# PPG_sensor.net
KiCad netlist of a schematic drawn in Altium Designer
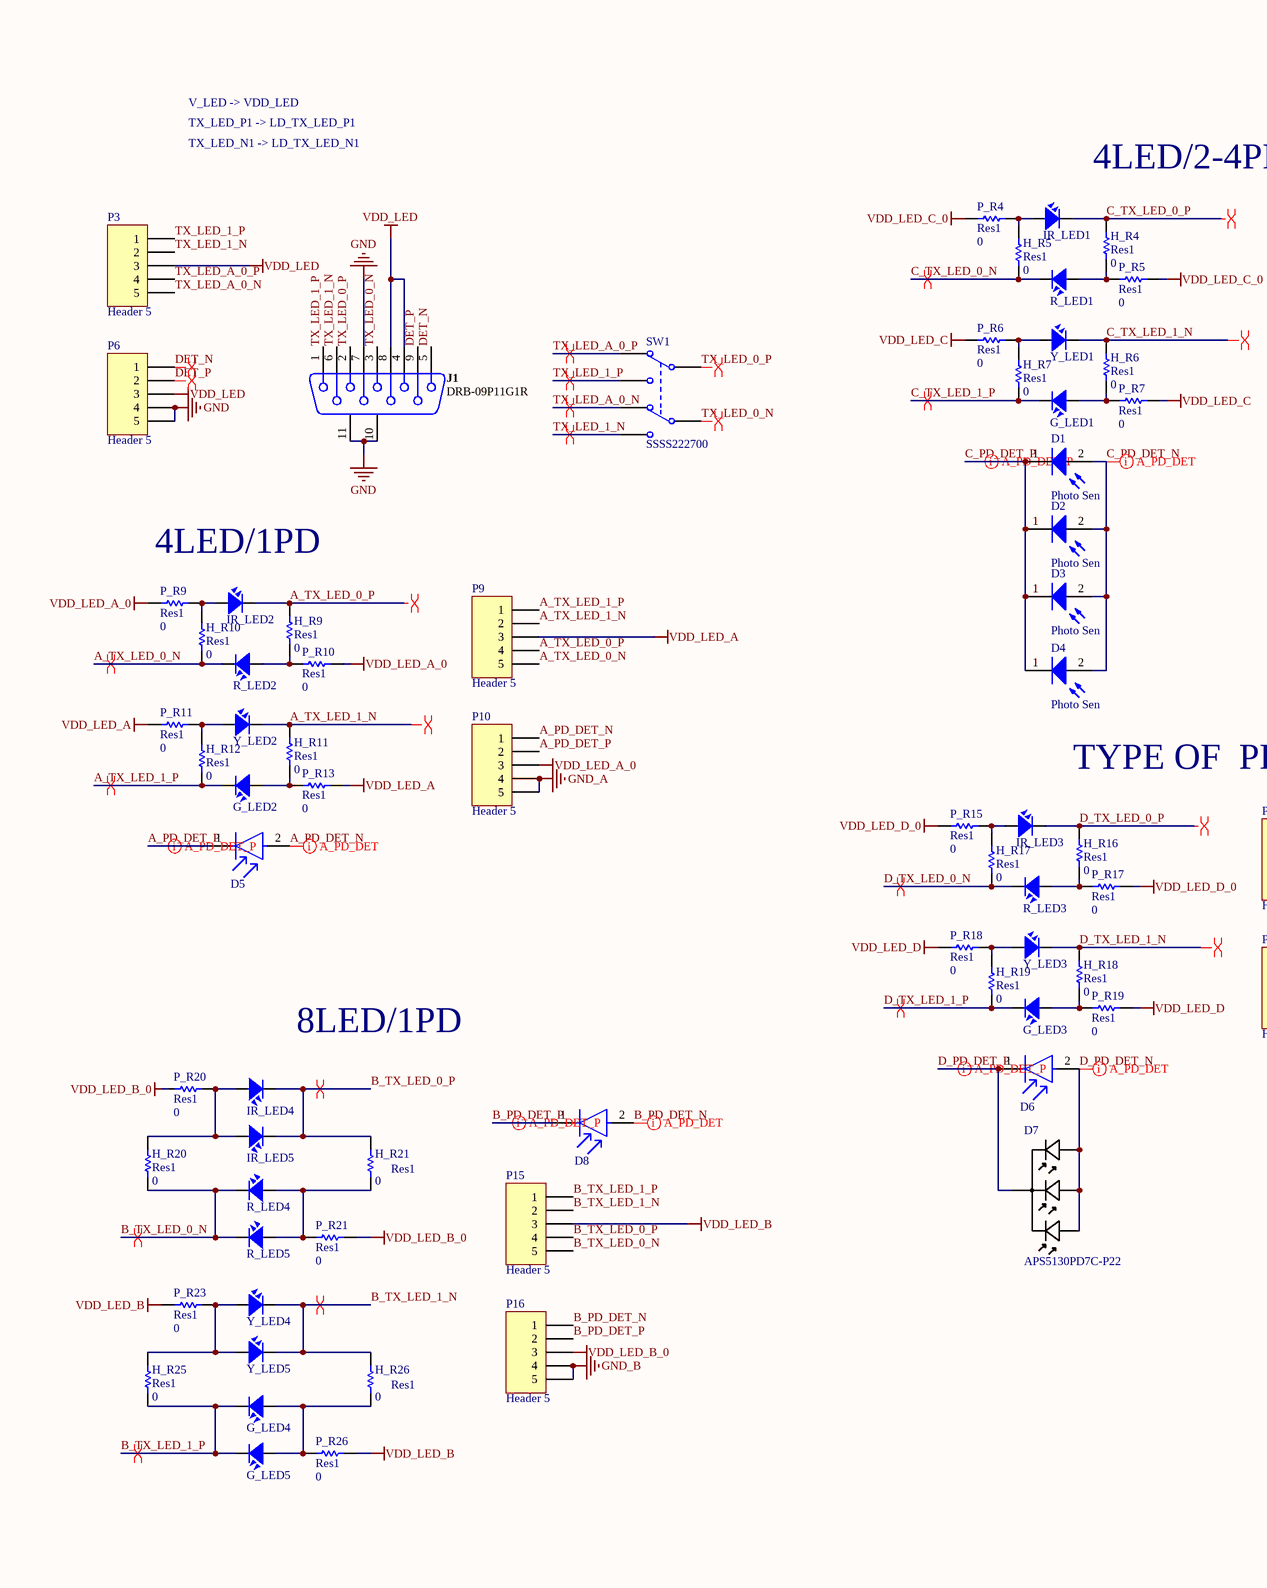
[diagram p0: PPG_sensor.SchDoc, left]
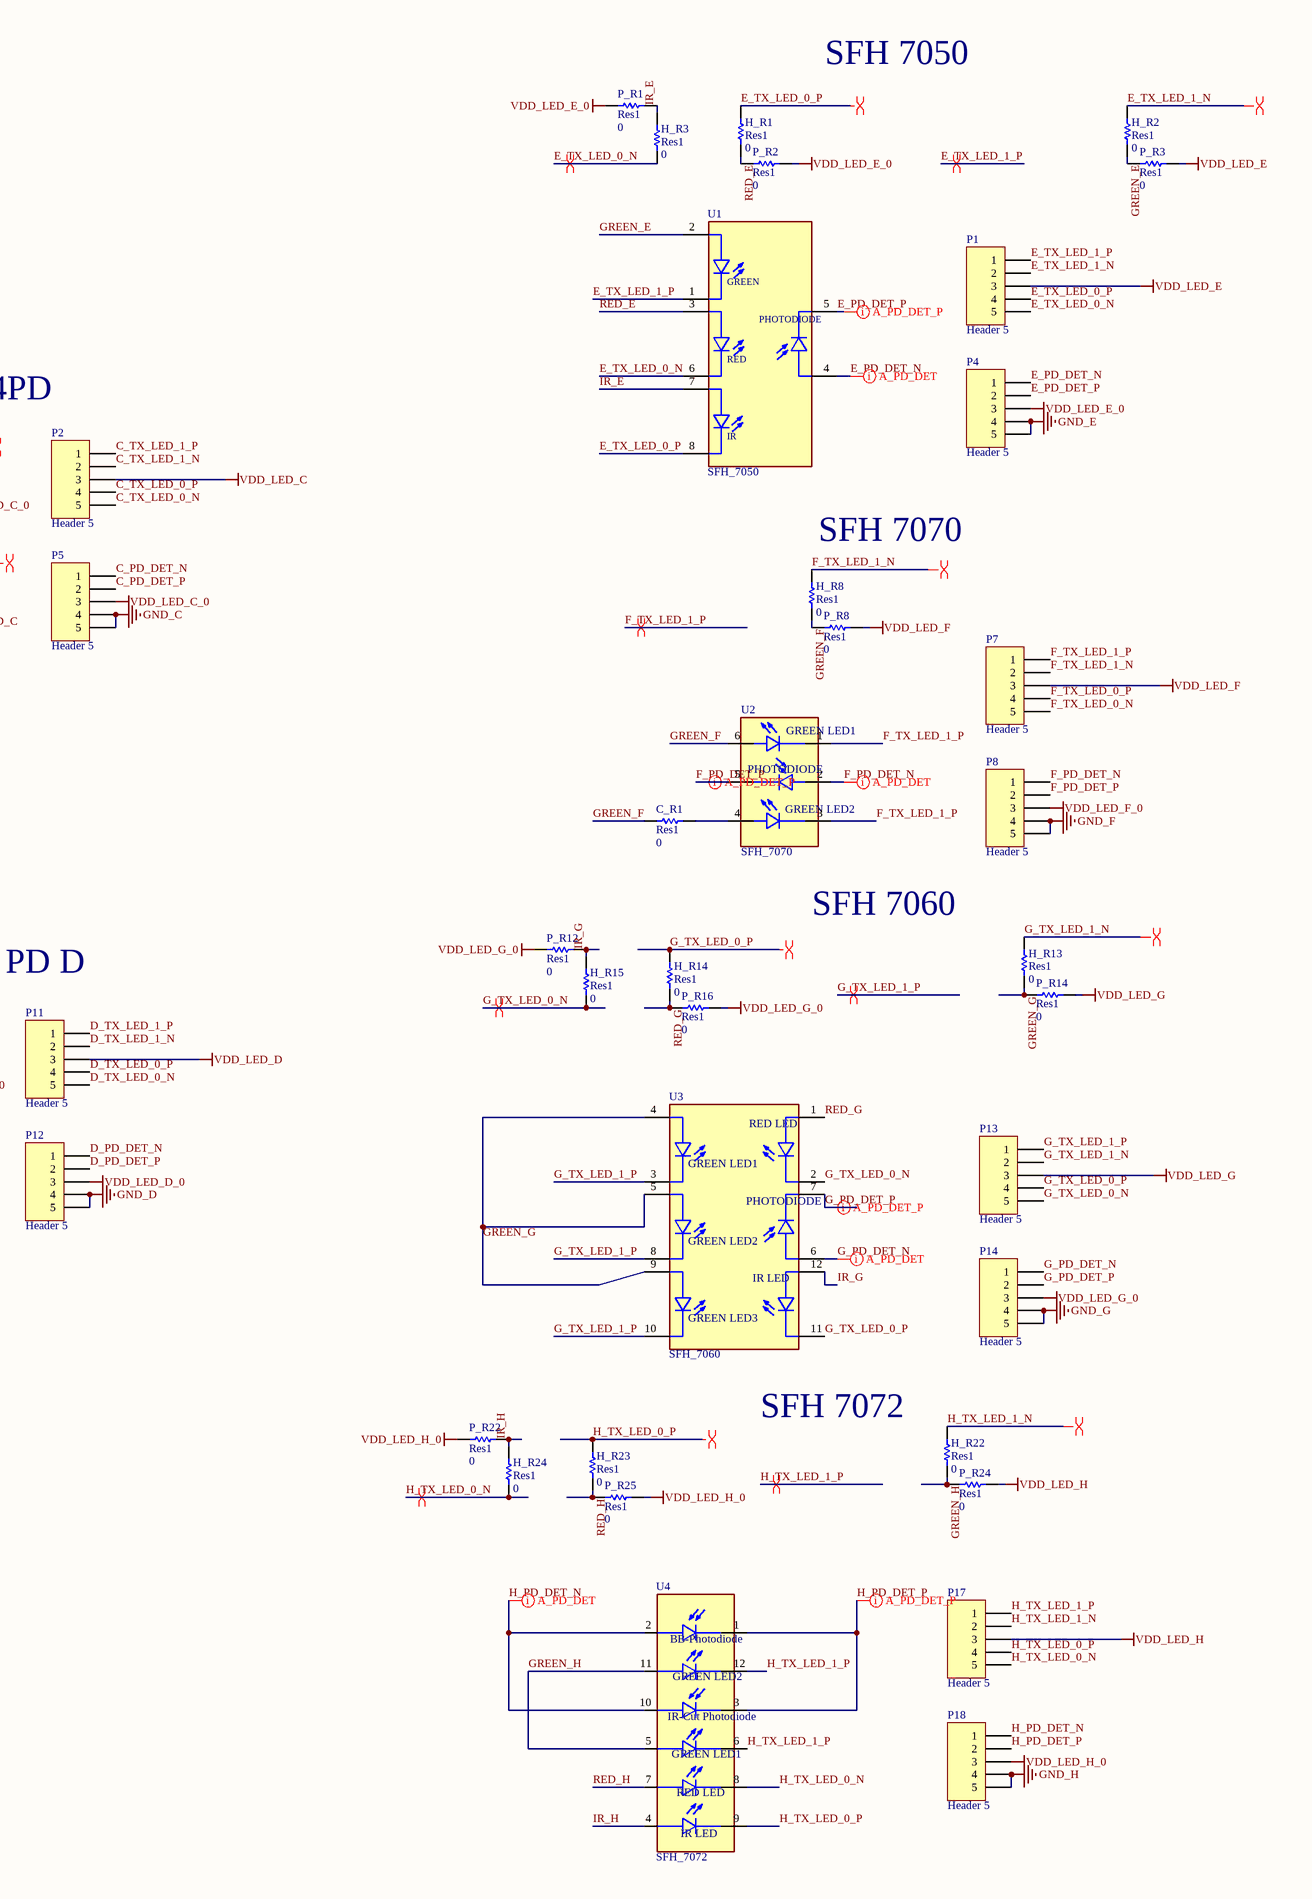
[diagram p1: PPG_sensor.SchDoc, right]

(export (version "E")
  (design (tool "Eeschema 10.0.6"))
  (components
    (comp (ref "C_R1")
      (value "Res1")
      (footprint "RES-SMD-0603")
      (description "Resistor")
      (fields (field (name "ALTIUM_VALUE") "0"))
      (libsource (lib "Miscellaneous Devices") (part "Res1"))
    )
    (comp (ref "D1")
      (value "Photo Sen")
      (footprint "PD_2704")
      (description "Photosensitive Diode")
      (libsource (lib "Miscellaneous Devices") (part "Photo Sen"))
    )
    (comp (ref "D2")
      (value "Photo Sen")
      (footprint "PD_2704")
      (description "Photosensitive Diode")
      (libsource (lib "Miscellaneous Devices") (part "Photo Sen"))
    )
    (comp (ref "D3")
      (value "Photo Sen")
      (footprint "PD_2704")
      (description "Photosensitive Diode")
      (libsource (lib "Miscellaneous Devices") (part "Photo Sen"))
    )
    (comp (ref "D4")
      (value "Photo Sen")
      (footprint "PD_2704")
      (description "Photosensitive Diode")
      (libsource (lib "Miscellaneous Devices") (part "Photo Sen"))
    )
    (comp (ref "D5")
      (value "SFH_2704")
      (footprint "OSRAM_Opto_Semiconductors_SFH_2704_MFG")
      (libsource (lib "Diode_OSRAM_Opto_Semiconductors_SFH_2704_eec") (part "SFH_2704"))
    )
    (comp (ref "D6")
      (value "SFH_2704")
      (footprint "OSRAM_Opto_Semiconductors_SFH_2704_MFG")
      (libsource (lib "Diode_OSRAM_Opto_Semiconductors_SFH_2704_eec") (part "SFH_2704"))
    )
    (comp (ref "D7")
      (value "APS5130PD7C-P22")
      (footprint "LED_APS5130PD7C-P22_KNB")
      (description "No Description Available")
      (libsource (lib "APS5130PD7C-P22") (part "APS5130PD7C-P22"))
    )
    (comp (ref "D8")
      (value "SFH_2704")
      (footprint "OSRAM_Opto_Semiconductors_SFH_2704_MFG")
      (libsource (lib "Diode_OSRAM_Opto_Semiconductors_SFH_2704_eec") (part "SFH_2704"))
    )
    (comp (ref "G_LED1")
      (value "LED")
      (footprint "RESC0402X15N")
      (libsource (lib "LIBRARY") (part "LED SMD"))
    )
    (comp (ref "G_LED2")
      (value "LED")
      (footprint "LED_PPG_DISTANCE_2")
      (libsource (lib "LIBRARY") (part "LED SMD"))
    )
    (comp (ref "G_LED3")
      (value "LED")
      (footprint "LED_PPG_DISTANCE_2")
      (libsource (lib "LIBRARY") (part "LED SMD"))
    )
    (comp (ref "G_LED4")
      (value "LED")
      (footprint "LED_PPG_DISTANCE_2")
      (libsource (lib "LIBRARY") (part "LED SMD"))
    )
    (comp (ref "G_LED5")
      (value "LED")
      (footprint "LED_PPG_DISTANCE_2")
      (libsource (lib "LIBRARY") (part "LED SMD"))
    )
    (comp (ref "H_R1")
      (value "Res1")
      (footprint "RES-SMD-0603")
      (description "Resistor")
      (fields (field (name "ALTIUM_VALUE") "0"))
      (libsource (lib "Miscellaneous Devices") (part "Res1"))
    )
    (comp (ref "H_R2")
      (value "Res1")
      (footprint "RES-SMD-0603")
      (description "Resistor")
      (fields (field (name "ALTIUM_VALUE") "0"))
      (libsource (lib "Miscellaneous Devices") (part "Res1"))
    )
    (comp (ref "H_R3")
      (value "Res1")
      (footprint "RES-SMD-0603")
      (description "Resistor")
      (fields (field (name "ALTIUM_VALUE") "0"))
      (libsource (lib "Miscellaneous Devices") (part "Res1"))
    )
    (comp (ref "H_R4")
      (value "Res1")
      (footprint "RES-SMD-0603")
      (description "Resistor")
      (fields (field (name "ALTIUM_VALUE") "0"))
      (libsource (lib "Miscellaneous Devices") (part "Res1"))
    )
    (comp (ref "H_R5")
      (value "Res1")
      (footprint "RES-SMD-0603")
      (description "Resistor")
      (fields (field (name "ALTIUM_VALUE") "0"))
      (libsource (lib "Miscellaneous Devices") (part "Res1"))
    )
    (comp (ref "H_R6")
      (value "Res1")
      (footprint "RES-SMD-0603")
      (description "Resistor")
      (fields (field (name "ALTIUM_VALUE") "0"))
      (libsource (lib "Miscellaneous Devices") (part "Res1"))
    )
    (comp (ref "H_R7")
      (value "Res1")
      (footprint "RES-SMD-0603")
      (description "Resistor")
      (fields (field (name "ALTIUM_VALUE") "0"))
      (libsource (lib "Miscellaneous Devices") (part "Res1"))
    )
    (comp (ref "H_R8")
      (value "Res1")
      (footprint "RES-SMD-0603")
      (description "Resistor")
      (fields (field (name "ALTIUM_VALUE") "0"))
      (libsource (lib "Miscellaneous Devices") (part "Res1"))
    )
    (comp (ref "H_R9")
      (value "Res1")
      (footprint "RES-SMD-0603")
      (description "Resistor")
      (fields (field (name "ALTIUM_VALUE") "0"))
      (libsource (lib "Miscellaneous Devices") (part "Res1"))
    )
    (comp (ref "H_R10")
      (value "Res1")
      (footprint "RES-SMD-0603")
      (description "Resistor")
      (fields (field (name "ALTIUM_VALUE") "0"))
      (libsource (lib "Miscellaneous Devices") (part "Res1"))
    )
    (comp (ref "H_R11")
      (value "Res1")
      (footprint "RES-SMD-0603")
      (description "Resistor")
      (fields (field (name "ALTIUM_VALUE") "0"))
      (libsource (lib "Miscellaneous Devices") (part "Res1"))
    )
    (comp (ref "H_R12")
      (value "Res1")
      (footprint "RES-SMD-0603")
      (description "Resistor")
      (fields (field (name "ALTIUM_VALUE") "0"))
      (libsource (lib "Miscellaneous Devices") (part "Res1"))
    )
    (comp (ref "H_R13")
      (value "Res1")
      (footprint "RES-SMD-0603")
      (description "Resistor")
      (fields (field (name "ALTIUM_VALUE") "0"))
      (libsource (lib "Miscellaneous Devices") (part "Res1"))
    )
    (comp (ref "H_R14")
      (value "Res1")
      (footprint "RES-SMD-0603")
      (description "Resistor")
      (fields (field (name "ALTIUM_VALUE") "0"))
      (libsource (lib "Miscellaneous Devices") (part "Res1"))
    )
    (comp (ref "H_R15")
      (value "Res1")
      (footprint "RES-SMD-0603")
      (description "Resistor")
      (fields (field (name "ALTIUM_VALUE") "0"))
      (libsource (lib "Miscellaneous Devices") (part "Res1"))
    )
    (comp (ref "H_R16")
      (value "Res1")
      (footprint "RES-SMD-0603")
      (description "Resistor")
      (fields (field (name "ALTIUM_VALUE") "0"))
      (libsource (lib "Miscellaneous Devices") (part "Res1"))
    )
    (comp (ref "H_R17")
      (value "Res1")
      (footprint "RES-SMD-0603")
      (description "Resistor")
      (fields (field (name "ALTIUM_VALUE") "0"))
      (libsource (lib "Miscellaneous Devices") (part "Res1"))
    )
    (comp (ref "H_R18")
      (value "Res1")
      (footprint "RES-SMD-0603")
      (description "Resistor")
      (fields (field (name "ALTIUM_VALUE") "0"))
      (libsource (lib "Miscellaneous Devices") (part "Res1"))
    )
    (comp (ref "H_R19")
      (value "Res1")
      (footprint "RES-SMD-0603")
      (description "Resistor")
      (fields (field (name "ALTIUM_VALUE") "0"))
      (libsource (lib "Miscellaneous Devices") (part "Res1"))
    )
    (comp (ref "H_R20")
      (value "Res1")
      (footprint "RES-SMD-0603")
      (description "Resistor")
      (fields (field (name "ALTIUM_VALUE") "0"))
      (libsource (lib "Miscellaneous Devices") (part "Res1"))
    )
    (comp (ref "H_R21")
      (value "Res1")
      (footprint "RES-SMD-0603")
      (description "Resistor")
      (fields (field (name "ALTIUM_VALUE") "0"))
      (libsource (lib "Miscellaneous Devices") (part "Res1"))
    )
    (comp (ref "H_R22")
      (value "Res1")
      (footprint "RES-SMD-0603")
      (description "Resistor")
      (fields (field (name "ALTIUM_VALUE") "0"))
      (libsource (lib "Miscellaneous Devices") (part "Res1"))
    )
    (comp (ref "H_R23")
      (value "Res1")
      (footprint "RES-SMD-0603")
      (description "Resistor")
      (fields (field (name "ALTIUM_VALUE") "0"))
      (libsource (lib "Miscellaneous Devices") (part "Res1"))
    )
    (comp (ref "H_R24")
      (value "Res1")
      (footprint "RES-SMD-0603")
      (description "Resistor")
      (fields (field (name "ALTIUM_VALUE") "0"))
      (libsource (lib "Miscellaneous Devices") (part "Res1"))
    )
    (comp (ref "H_R25")
      (value "Res1")
      (footprint "RES-SMD-0603")
      (description "Resistor")
      (fields (field (name "ALTIUM_VALUE") "0"))
      (libsource (lib "Miscellaneous Devices") (part "Res1"))
    )
    (comp (ref "H_R26")
      (value "Res1")
      (footprint "RES-SMD-0603")
      (description "Resistor")
      (fields (field (name "ALTIUM_VALUE") "0"))
      (libsource (lib "Miscellaneous Devices") (part "Res1"))
    )
    (comp (ref "IR_LED1")
      (value "LED")
      (footprint "RESC0402X15N")
      (libsource (lib "LIBRARY") (part "LED SMD"))
    )
    (comp (ref "IR_LED2")
      (value "LED")
      (footprint "LED_PPG_DISTANCE_2")
      (libsource (lib "LIBRARY") (part "LED SMD"))
    )
    (comp (ref "IR_LED3")
      (value "LED")
      (footprint "LED_PPG_DISTANCE_2")
      (libsource (lib "LIBRARY") (part "LED SMD"))
    )
    (comp (ref "IR_LED4")
      (value "LED")
      (footprint "LED_PPG_DISTANCE_2")
      (libsource (lib "LIBRARY") (part "LED SMD"))
    )
    (comp (ref "IR_LED5")
      (value "LED")
      (footprint "LED_PPG_DISTANCE_2")
      (libsource (lib "LIBRARY") (part "LED SMD"))
    )
    (comp (ref "J1")
      (value "DRB-09P11G1R")
      (footprint "K202XHT-E9P-NJ_DB9_Male")
      (description "Connector, DB9 R/A Through-hole Male")
      (libsource (lib "LIBRARY") (part "CON 9 Male"))
    )
    (comp (ref "P1")
      (value "Header 5")
      (footprint "HDR 5 POS 1 ROW")
      (description "Header, 5-Pin")
      (libsource (lib "Miscellaneous Connectors") (part "Header 5"))
    )
    (comp (ref "P2")
      (value "Header 5")
      (footprint "HDR 5 POS 1 ROW")
      (description "Header, 5-Pin")
      (libsource (lib "Miscellaneous Connectors") (part "Header 5"))
    )
    (comp (ref "P3")
      (value "Header 5")
      (footprint "HDR1X5")
      (description "Header, 5-Pin")
      (libsource (lib "Miscellaneous Connectors") (part "Header 5"))
    )
    (comp (ref "P4")
      (value "Header 5")
      (footprint "HDR 5 POS 1 ROW")
      (description "Header, 5-Pin")
      (libsource (lib "Miscellaneous Connectors") (part "Header 5"))
    )
    (comp (ref "P5")
      (value "Header 5")
      (footprint "HDR 5 POS 1 ROW")
      (description "Header, 5-Pin")
      (libsource (lib "Miscellaneous Connectors") (part "Header 5"))
    )
    (comp (ref "P6")
      (value "Header 5")
      (footprint "HDR1X5")
      (description "Header, 5-Pin")
      (libsource (lib "Miscellaneous Connectors") (part "Header 5"))
    )
    (comp (ref "P7")
      (value "Header 5")
      (footprint "HDR 5 POS 1 ROW")
      (description "Header, 5-Pin")
      (libsource (lib "Miscellaneous Connectors") (part "Header 5"))
    )
    (comp (ref "P8")
      (value "Header 5")
      (footprint "HDR 5 POS 1 ROW")
      (description "Header, 5-Pin")
      (libsource (lib "Miscellaneous Connectors") (part "Header 5"))
    )
    (comp (ref "P9")
      (value "Header 5")
      (footprint "HDR 5 POS 1 ROW")
      (description "Header, 5-Pin")
      (libsource (lib "Miscellaneous Connectors") (part "Header 5"))
    )
    (comp (ref "P10")
      (value "Header 5")
      (footprint "HDR 5 POS 1 ROW")
      (description "Header, 5-Pin")
      (libsource (lib "Miscellaneous Connectors") (part "Header 5"))
    )
    (comp (ref "P11")
      (value "Header 5")
      (footprint "HDR 5 POS 1 ROW")
      (description "Header, 5-Pin")
      (libsource (lib "Miscellaneous Connectors") (part "Header 5"))
    )
    (comp (ref "P12")
      (value "Header 5")
      (footprint "HDR 5 POS 1 ROW")
      (description "Header, 5-Pin")
      (libsource (lib "Miscellaneous Connectors") (part "Header 5"))
    )
    (comp (ref "P13")
      (value "Header 5")
      (footprint "HDR 5 POS 1 ROW")
      (description "Header, 5-Pin")
      (libsource (lib "Miscellaneous Connectors") (part "Header 5"))
    )
    (comp (ref "P14")
      (value "Header 5")
      (footprint "HDR 5 POS 1 ROW")
      (description "Header, 5-Pin")
      (libsource (lib "Miscellaneous Connectors") (part "Header 5"))
    )
    (comp (ref "P15")
      (value "Header 5")
      (footprint "HDR 5 POS 1 ROW")
      (description "Header, 5-Pin")
      (libsource (lib "Miscellaneous Connectors") (part "Header 5"))
    )
    (comp (ref "P16")
      (value "Header 5")
      (footprint "HDR 5 POS 1 ROW")
      (description "Header, 5-Pin")
      (libsource (lib "Miscellaneous Connectors") (part "Header 5"))
    )
    (comp (ref "P17")
      (value "Header 5")
      (footprint "HDR 5 POS 1 ROW")
      (description "Header, 5-Pin")
      (libsource (lib "Miscellaneous Connectors") (part "Header 5"))
    )
    (comp (ref "P18")
      (value "Header 5")
      (footprint "HDR 5 POS 1 ROW")
      (description "Header, 5-Pin")
      (libsource (lib "Miscellaneous Connectors") (part "Header 5"))
    )
    (comp (ref "P_R1")
      (value "Res1")
      (footprint "RES-SMD-0603")
      (description "Resistor")
      (fields (field (name "ALTIUM_VALUE") "0"))
      (libsource (lib "Miscellaneous Devices") (part "Res1"))
    )
    (comp (ref "P_R2")
      (value "Res1")
      (footprint "RES-SMD-0603")
      (description "Resistor")
      (fields (field (name "ALTIUM_VALUE") "0"))
      (libsource (lib "Miscellaneous Devices") (part "Res1"))
    )
    (comp (ref "P_R3")
      (value "Res1")
      (footprint "RES-SMD-0603")
      (description "Resistor")
      (fields (field (name "ALTIUM_VALUE") "0"))
      (libsource (lib "Miscellaneous Devices") (part "Res1"))
    )
    (comp (ref "P_R4")
      (value "Res1")
      (footprint "RES-SMD-0603")
      (description "Resistor")
      (fields (field (name "ALTIUM_VALUE") "0"))
      (libsource (lib "Miscellaneous Devices") (part "Res1"))
    )
    (comp (ref "P_R5")
      (value "Res1")
      (footprint "RES-SMD-0603")
      (description "Resistor")
      (fields (field (name "ALTIUM_VALUE") "0"))
      (libsource (lib "Miscellaneous Devices") (part "Res1"))
    )
    (comp (ref "P_R6")
      (value "Res1")
      (footprint "RES-SMD-0603")
      (description "Resistor")
      (fields (field (name "ALTIUM_VALUE") "0"))
      (libsource (lib "Miscellaneous Devices") (part "Res1"))
    )
    (comp (ref "P_R7")
      (value "Res1")
      (footprint "RES-SMD-0603")
      (description "Resistor")
      (fields (field (name "ALTIUM_VALUE") "0"))
      (libsource (lib "Miscellaneous Devices") (part "Res1"))
    )
    (comp (ref "P_R8")
      (value "Res1")
      (footprint "RES-SMD-0603")
      (description "Resistor")
      (fields (field (name "ALTIUM_VALUE") "0"))
      (libsource (lib "Miscellaneous Devices") (part "Res1"))
    )
    (comp (ref "P_R9")
      (value "Res1")
      (footprint "RES-SMD-0603")
      (description "Resistor")
      (fields (field (name "ALTIUM_VALUE") "0"))
      (libsource (lib "Miscellaneous Devices") (part "Res1"))
    )
    (comp (ref "P_R10")
      (value "Res1")
      (footprint "RES-SMD-0603")
      (description "Resistor")
      (fields (field (name "ALTIUM_VALUE") "0"))
      (libsource (lib "Miscellaneous Devices") (part "Res1"))
    )
    (comp (ref "P_R11")
      (value "Res1")
      (footprint "RES-SMD-0603")
      (description "Resistor")
      (fields (field (name "ALTIUM_VALUE") "0"))
      (libsource (lib "Miscellaneous Devices") (part "Res1"))
    )
    (comp (ref "P_R12")
      (value "Res1")
      (footprint "RES-SMD-0603")
      (description "Resistor")
      (fields (field (name "ALTIUM_VALUE") "0"))
      (libsource (lib "Miscellaneous Devices") (part "Res1"))
    )
    (comp (ref "P_R13")
      (value "Res1")
      (footprint "RES-SMD-0603")
      (description "Resistor")
      (fields (field (name "ALTIUM_VALUE") "0"))
      (libsource (lib "Miscellaneous Devices") (part "Res1"))
    )
    (comp (ref "P_R14")
      (value "Res1")
      (footprint "RES-SMD-0603")
      (description "Resistor")
      (fields (field (name "ALTIUM_VALUE") "0"))
      (libsource (lib "Miscellaneous Devices") (part "Res1"))
    )
    (comp (ref "P_R15")
      (value "Res1")
      (footprint "RES-SMD-0603")
      (description "Resistor")
      (fields (field (name "ALTIUM_VALUE") "0"))
      (libsource (lib "Miscellaneous Devices") (part "Res1"))
    )
    (comp (ref "P_R16")
      (value "Res1")
      (footprint "RES-SMD-0603")
      (description "Resistor")
      (fields (field (name "ALTIUM_VALUE") "0"))
      (libsource (lib "Miscellaneous Devices") (part "Res1"))
    )
    (comp (ref "P_R17")
      (value "Res1")
      (footprint "RES-SMD-0603")
      (description "Resistor")
      (fields (field (name "ALTIUM_VALUE") "0"))
      (libsource (lib "Miscellaneous Devices") (part "Res1"))
    )
    (comp (ref "P_R18")
      (value "Res1")
      (footprint "RES-SMD-0603")
      (description "Resistor")
      (fields (field (name "ALTIUM_VALUE") "0"))
      (libsource (lib "Miscellaneous Devices") (part "Res1"))
    )
    (comp (ref "P_R19")
      (value "Res1")
      (footprint "RES-SMD-0603")
      (description "Resistor")
      (fields (field (name "ALTIUM_VALUE") "0"))
      (libsource (lib "Miscellaneous Devices") (part "Res1"))
    )
    (comp (ref "P_R20")
      (value "Res1")
      (footprint "RES-SMD-0603")
      (description "Resistor")
      (fields (field (name "ALTIUM_VALUE") "0"))
      (libsource (lib "Miscellaneous Devices") (part "Res1"))
    )
    (comp (ref "P_R21")
      (value "Res1")
      (footprint "RES-SMD-0603")
      (description "Resistor")
      (fields (field (name "ALTIUM_VALUE") "0"))
      (libsource (lib "Miscellaneous Devices") (part "Res1"))
    )
    (comp (ref "P_R22")
      (value "Res1")
      (footprint "RES-SMD-0603")
      (description "Resistor")
      (fields (field (name "ALTIUM_VALUE") "0"))
      (libsource (lib "Miscellaneous Devices") (part "Res1"))
    )
    (comp (ref "P_R23")
      (value "Res1")
      (footprint "RES-SMD-0603")
      (description "Resistor")
      (fields (field (name "ALTIUM_VALUE") "0"))
      (libsource (lib "Miscellaneous Devices") (part "Res1"))
    )
    (comp (ref "P_R24")
      (value "Res1")
      (footprint "RES-SMD-0603")
      (description "Resistor")
      (fields (field (name "ALTIUM_VALUE") "0"))
      (libsource (lib "Miscellaneous Devices") (part "Res1"))
    )
    (comp (ref "P_R25")
      (value "Res1")
      (footprint "RES-SMD-0603")
      (description "Resistor")
      (fields (field (name "ALTIUM_VALUE") "0"))
      (libsource (lib "Miscellaneous Devices") (part "Res1"))
    )
    (comp (ref "P_R26")
      (value "Res1")
      (footprint "RES-SMD-0603")
      (description "Resistor")
      (fields (field (name "ALTIUM_VALUE") "0"))
      (libsource (lib "Miscellaneous Devices") (part "Res1"))
    )
    (comp (ref "R_LED1")
      (value "LED")
      (footprint "RESC0402X15N")
      (libsource (lib "LIBRARY") (part "LED SMD"))
    )
    (comp (ref "R_LED2")
      (value "LED")
      (footprint "LED_PPG_DISTANCE_2")
      (libsource (lib "LIBRARY") (part "LED SMD"))
    )
    (comp (ref "R_LED3")
      (value "LED")
      (footprint "LED_PPG_DISTANCE_2")
      (libsource (lib "LIBRARY") (part "LED SMD"))
    )
    (comp (ref "R_LED4")
      (value "LED")
      (footprint "LED_PPG_DISTANCE_2")
      (libsource (lib "LIBRARY") (part "LED SMD"))
    )
    (comp (ref "R_LED5")
      (value "LED")
      (footprint "LED_PPG_DISTANCE_2")
      (libsource (lib "LIBRARY") (part "LED SMD"))
    )
    (comp (ref "SW1")
      (value "SSSS222700")
      (footprint "DPDT_SSSS222700")
      (libsource (lib "SF_lib") (part "SSSS222700"))
    )
    (comp (ref "U1")
      (value "SFH_7050")
      (footprint "XDCR_SFH_7050")
      (description "Salida de voltaje del sensor de oxÃ­metro / frecuencia cardÃ­aca")
      (fields (field (name "DIGI-KEY_PART_NUMBER") "475-3346-1-ND") (field (name "MP") "SFH 7050"))
      (libsource (lib "SFH_7050") (part "SFH_7050"))
    )
    (comp (ref "U2")
      (value "SFH_7070")
      (footprint "XDCR_SFH_7070")
      (description "Reflective Optical Sensor 6-SMD, No Lead")
      (fields (field (name "MP") "SFH 7070") (field (name "MF") "OSRAM Opto"))
      (libsource (lib "SFH_7070") (part "SFH_7070"))
    )
    (comp (ref "U3")
      (value "SFH_7060")
      (footprint "XDCR_SFH_7060")
      (description "Oximeter/Heart Rate Sensor Current Output")
      (fields (field (name "MP") "SFH 7060") (field (name "MF") "OSRAM Opto"))
      (libsource (lib "SFH_7060") (part "SFH_7060"))
    )
    (comp (ref "U4")
      (value "SFH_7072")
      (footprint "XDCR_SFH_7072")
      (description "Reflective Optical Sensor 6-SMD, No Lead")
      (fields (field (name "MP") "SFH 7072") (field (name "MF") "OSRAM Opto"))
      (libsource (lib "SFH_7072") (part "SFH_7072"))
    )
    (comp (ref "Y_LED1")
      (value "LED")
      (footprint "RESC0402X15N")
      (libsource (lib "LIBRARY") (part "LED SMD"))
    )
    (comp (ref "Y_LED2")
      (value "LED")
      (footprint "LED_PPG_DISTANCE_2")
      (libsource (lib "LIBRARY") (part "LED SMD"))
    )
    (comp (ref "Y_LED3")
      (value "LED")
      (footprint "LED_PPG_DISTANCE_2")
      (libsource (lib "LIBRARY") (part "LED SMD"))
    )
    (comp (ref "Y_LED4")
      (value "LED")
      (footprint "LED_PPG_DISTANCE_2")
      (libsource (lib "LIBRARY") (part "LED SMD"))
    )
    (comp (ref "Y_LED5")
      (value "LED")
      (footprint "LED_PPG_DISTANCE_2")
      (libsource (lib "LIBRARY") (part "LED SMD"))
    )
  )
  (nets
    (net (code "1") (name "/A_PD_DET_N") (class "Default")
      (node (ref "D5") (pin "2") (pinfunction "A_2") (pintype "passive"))
      (node (ref "P10") (pin "1") (pinfunction "1_1") (pintype "passive"))
    )
    (net (code "2") (name "/A_PD_DET_P") (class "Default")
      (node (ref "D5") (pin "1") (pinfunction "C_1") (pintype "passive"))
      (node (ref "P10") (pin "2") (pinfunction "2_2") (pintype "passive"))
    )
    (net (code "3") (name "/A_TX_LED_0_N") (class "Default")
      (node (ref "H_R10") (pin "2") (pinfunction "2_2") (pintype "passive"))
      (node (ref "P9") (pin "5") (pinfunction "5_5") (pintype "passive"))
      (node (ref "R_LED2") (pin "2") (pinfunction "2_2") (pintype "passive"))
    )
    (net (code "4") (name "/A_TX_LED_0_P") (class "Default")
      (node (ref "H_R9") (pin "1") (pinfunction "1_1") (pintype "passive"))
      (node (ref "IR_LED2") (pin "2") (pinfunction "2_2") (pintype "passive"))
      (node (ref "P9") (pin "4") (pinfunction "4_4") (pintype "passive"))
    )
    (net (code "5") (name "/A_TX_LED_1_N") (class "Default")
      (node (ref "H_R11") (pin "1") (pinfunction "1_1") (pintype "passive"))
      (node (ref "P9") (pin "2") (pinfunction "2_2") (pintype "passive"))
      (node (ref "Y_LED2") (pin "2") (pinfunction "2_2") (pintype "passive"))
    )
    (net (code "6") (name "/A_TX_LED_1_P") (class "Default")
      (node (ref "G_LED2") (pin "2") (pinfunction "2_2") (pintype "passive"))
      (node (ref "H_R12") (pin "2") (pinfunction "2_2") (pintype "passive"))
      (node (ref "P9") (pin "1") (pinfunction "1_1") (pintype "passive"))
    )
    (net (code "7") (name "/B_PD_DET_N") (class "Default")
      (node (ref "D8") (pin "2") (pinfunction "A_2") (pintype "passive"))
      (node (ref "P16") (pin "1") (pinfunction "1_1") (pintype "passive"))
    )
    (net (code "8") (name "/B_PD_DET_P") (class "Default")
      (node (ref "D8") (pin "1") (pinfunction "C_1") (pintype "passive"))
      (node (ref "P16") (pin "2") (pinfunction "2_2") (pintype "passive"))
    )
    (net (code "9") (name "/B_TX_LED_0_N") (class "Default")
      (node (ref "H_R20") (pin "2") (pinfunction "2_2") (pintype "passive"))
      (node (ref "P15") (pin "5") (pinfunction "5_5") (pintype "passive"))
      (node (ref "R_LED4") (pin "2") (pinfunction "2_2") (pintype "passive"))
      (node (ref "R_LED5") (pin "2") (pinfunction "2_2") (pintype "passive"))
    )
    (net (code "10") (name "/B_TX_LED_0_P") (class "Default")
      (node (ref "H_R21") (pin "1") (pinfunction "1_1") (pintype "passive"))
      (node (ref "IR_LED4") (pin "2") (pinfunction "2_2") (pintype "passive"))
      (node (ref "IR_LED5") (pin "2") (pinfunction "2_2") (pintype "passive"))
      (node (ref "P15") (pin "4") (pinfunction "4_4") (pintype "passive"))
    )
    (net (code "11") (name "/B_TX_LED_1_N") (class "Default")
      (node (ref "H_R26") (pin "1") (pinfunction "1_1") (pintype "passive"))
      (node (ref "P15") (pin "2") (pinfunction "2_2") (pintype "passive"))
      (node (ref "Y_LED4") (pin "2") (pinfunction "2_2") (pintype "passive"))
      (node (ref "Y_LED5") (pin "2") (pinfunction "2_2") (pintype "passive"))
    )
    (net (code "12") (name "/B_TX_LED_1_P") (class "Default")
      (node (ref "G_LED4") (pin "2") (pinfunction "2_2") (pintype "passive"))
      (node (ref "G_LED5") (pin "2") (pinfunction "2_2") (pintype "passive"))
      (node (ref "H_R25") (pin "2") (pinfunction "2_2") (pintype "passive"))
      (node (ref "P15") (pin "1") (pinfunction "1_1") (pintype "passive"))
    )
    (net (code "13") (name "/C_PD_DET_N") (class "Default")
      (node (ref "D1") (pin "2") (pinfunction "A_2") (pintype "passive"))
      (node (ref "D2") (pin "2") (pinfunction "A_2") (pintype "passive"))
      (node (ref "D3") (pin "2") (pinfunction "A_2") (pintype "passive"))
      (node (ref "D4") (pin "2") (pinfunction "A_2") (pintype "passive"))
      (node (ref "P5") (pin "1") (pinfunction "1_1") (pintype "passive"))
    )
    (net (code "14") (name "/C_PD_DET_P") (class "Default")
      (node (ref "D1") (pin "1") (pinfunction "K_1") (pintype "passive"))
      (node (ref "D2") (pin "1") (pinfunction "K_1") (pintype "passive"))
      (node (ref "D3") (pin "1") (pinfunction "K_1") (pintype "passive"))
      (node (ref "D4") (pin "1") (pinfunction "K_1") (pintype "passive"))
      (node (ref "P5") (pin "2") (pinfunction "2_2") (pintype "passive"))
    )
    (net (code "15") (name "/C_TX_LED_0_N") (class "Default")
      (node (ref "H_R5") (pin "2") (pinfunction "2_2") (pintype "passive"))
      (node (ref "P2") (pin "5") (pinfunction "5_5") (pintype "passive"))
      (node (ref "R_LED1") (pin "2") (pinfunction "2_2") (pintype "passive"))
    )
    (net (code "16") (name "/C_TX_LED_0_P") (class "Default")
      (node (ref "H_R4") (pin "1") (pinfunction "1_1") (pintype "passive"))
      (node (ref "IR_LED1") (pin "2") (pinfunction "2_2") (pintype "passive"))
      (node (ref "P2") (pin "4") (pinfunction "4_4") (pintype "passive"))
    )
    (net (code "17") (name "/C_TX_LED_1_N") (class "Default")
      (node (ref "H_R6") (pin "1") (pinfunction "1_1") (pintype "passive"))
      (node (ref "P2") (pin "2") (pinfunction "2_2") (pintype "passive"))
      (node (ref "Y_LED1") (pin "2") (pinfunction "2_2") (pintype "passive"))
    )
    (net (code "18") (name "/C_TX_LED_1_P") (class "Default")
      (node (ref "G_LED1") (pin "2") (pinfunction "2_2") (pintype "passive"))
      (node (ref "H_R7") (pin "2") (pinfunction "2_2") (pintype "passive"))
      (node (ref "P2") (pin "1") (pinfunction "1_1") (pintype "passive"))
    )
    (net (code "19") (name "/DET_N") (class "Default")
      (node (ref "J1") (pin "5") (pinfunction "5_5") (pintype "passive"))
      (node (ref "P6") (pin "1") (pinfunction "1_1") (pintype "passive"))
    )
    (net (code "20") (name "/DET_P") (class "Default")
      (node (ref "J1") (pin "9") (pinfunction "9_9") (pintype "passive"))
      (node (ref "P6") (pin "2") (pinfunction "2_2") (pintype "passive"))
    )
    (net (code "21") (name "/D_PD_DET_N") (class "Default")
      (node (ref "D6") (pin "2") (pinfunction "A_2") (pintype "passive"))
      (node (ref "D7") (pin "1") (pinfunction "1_1") (pintype "passive"))
      (node (ref "D7") (pin "2") (pinfunction "2_2") (pintype "passive"))
      (node (ref "D7") (pin "3") (pinfunction "3_3") (pintype "passive"))
      (node (ref "P12") (pin "1") (pinfunction "1_1") (pintype "passive"))
    )
    (net (code "22") (name "/D_PD_DET_P") (class "Default")
      (node (ref "D6") (pin "1") (pinfunction "C_1") (pintype "passive"))
      (node (ref "D7") (pin "4") (pinfunction "4_4") (pintype "passive"))
      (node (ref "P12") (pin "2") (pinfunction "2_2") (pintype "passive"))
    )
    (net (code "23") (name "/D_TX_LED_0_N") (class "Default")
      (node (ref "H_R17") (pin "2") (pinfunction "2_2") (pintype "passive"))
      (node (ref "P11") (pin "5") (pinfunction "5_5") (pintype "passive"))
      (node (ref "R_LED3") (pin "2") (pinfunction "2_2") (pintype "passive"))
    )
    (net (code "24") (name "/D_TX_LED_0_P") (class "Default")
      (node (ref "H_R16") (pin "1") (pinfunction "1_1") (pintype "passive"))
      (node (ref "IR_LED3") (pin "2") (pinfunction "2_2") (pintype "passive"))
      (node (ref "P11") (pin "4") (pinfunction "4_4") (pintype "passive"))
    )
    (net (code "25") (name "/D_TX_LED_1_N") (class "Default")
      (node (ref "H_R18") (pin "1") (pinfunction "1_1") (pintype "passive"))
      (node (ref "P11") (pin "2") (pinfunction "2_2") (pintype "passive"))
      (node (ref "Y_LED3") (pin "2") (pinfunction "2_2") (pintype "passive"))
    )
    (net (code "26") (name "/D_TX_LED_1_P") (class "Default")
      (node (ref "G_LED3") (pin "2") (pinfunction "2_2") (pintype "passive"))
      (node (ref "H_R19") (pin "2") (pinfunction "2_2") (pintype "passive"))
      (node (ref "P11") (pin "1") (pinfunction "1_1") (pintype "passive"))
    )
    (net (code "27") (name "/E_PD_DET_N") (class "Default")
      (node (ref "P4") (pin "1") (pinfunction "1_1") (pintype "passive"))
      (node (ref "U1") (pin "4") (pinfunction "PA_4") (pintype "passive"))
    )
    (net (code "28") (name "/E_PD_DET_P") (class "Default")
      (node (ref "P4") (pin "2") (pinfunction "2_2") (pintype "passive"))
      (node (ref "U1") (pin "5") (pinfunction "PC_5") (pintype "passive"))
    )
    (net (code "29") (name "/E_TX_LED_0_N") (class "Default")
      (node (ref "H_R3") (pin "2") (pinfunction "2_2") (pintype "passive"))
      (node (ref "P1") (pin "5") (pinfunction "5_5") (pintype "passive"))
      (node (ref "U1") (pin "6") (pinfunction "RC_6") (pintype "passive"))
    )
    (net (code "30") (name "/E_TX_LED_0_P") (class "Default")
      (node (ref "H_R1") (pin "1") (pinfunction "1_1") (pintype "passive"))
      (node (ref "P1") (pin "4") (pinfunction "4_4") (pintype "passive"))
      (node (ref "U1") (pin "8") (pinfunction "IC_8") (pintype "passive"))
    )
    (net (code "31") (name "/E_TX_LED_1_N") (class "Default")
      (node (ref "H_R2") (pin "1") (pinfunction "1_1") (pintype "passive"))
      (node (ref "P1") (pin "2") (pinfunction "2_2") (pintype "passive"))
    )
    (net (code "32") (name "/E_TX_LED_1_P") (class "Default")
      (node (ref "P1") (pin "1") (pinfunction "1_1") (pintype "passive"))
      (node (ref "U1") (pin "1") (pinfunction "GC_1") (pintype "passive"))
    )
    (net (code "33") (name "/F_PD_DET_N") (class "Default")
      (node (ref "P8") (pin "1") (pinfunction "1_1") (pintype "passive"))
      (node (ref "U2") (pin "2") (pinfunction "PA_2") (pintype "passive"))
    )
    (net (code "34") (name "/F_PD_DET_P") (class "Default")
      (node (ref "P8") (pin "2") (pinfunction "2_2") (pintype "passive"))
      (node (ref "U2") (pin "5") (pinfunction "PC_5") (pintype "passive"))
    )
    (net (code "35") (name "/F_TX_LED_0_N") (class "Default")
      (node (ref "P7") (pin "5") (pinfunction "5_5") (pintype "passive"))
    )
    (net (code "36") (name "/F_TX_LED_0_P") (class "Default")
      (node (ref "P7") (pin "4") (pinfunction "4_4") (pintype "passive"))
    )
    (net (code "37") (name "/F_TX_LED_1_N") (class "Default")
      (node (ref "H_R8") (pin "1") (pinfunction "1_1") (pintype "passive"))
      (node (ref "P7") (pin "2") (pinfunction "2_2") (pintype "passive"))
    )
    (net (code "38") (name "/F_TX_LED_1_P") (class "Default")
      (node (ref "P7") (pin "1") (pinfunction "1_1") (pintype "passive"))
      (node (ref "U2") (pin "1") (pinfunction "G1C_1") (pintype "passive"))
      (node (ref "U2") (pin "3") (pinfunction "G2C_3") (pintype "passive"))
    )
    (net (code "39") (name "/GREEN_E") (class "Default")
      (node (ref "H_R2") (pin "2") (pinfunction "2_2") (pintype "passive"))
      (node (ref "P_R3") (pin "1") (pinfunction "1_1") (pintype "passive"))
      (node (ref "U1") (pin "2") (pinfunction "GA_2") (pintype "passive"))
    )
    (net (code "40") (name "/GREEN_F") (class "Default")
      (node (ref "C_R1") (pin "1") (pinfunction "1_1") (pintype "passive"))
      (node (ref "H_R8") (pin "2") (pinfunction "2_2") (pintype "passive"))
      (node (ref "P_R8") (pin "1") (pinfunction "1_1") (pintype "passive"))
      (node (ref "U2") (pin "6") (pinfunction "G1A_6") (pintype "passive"))
    )
    (net (code "41") (name "/GREEN_G") (class "Default")
      (node (ref "H_R13") (pin "2") (pinfunction "2_2") (pintype "passive"))
      (node (ref "P_R14") (pin "1") (pinfunction "1_1") (pintype "passive"))
      (node (ref "U3") (pin "4") (pinfunction "G1A_4") (pintype "passive"))
      (node (ref "U3") (pin "5") (pinfunction "G2A_5") (pintype "passive"))
      (node (ref "U3") (pin "9") (pinfunction "G3A_9") (pintype "passive"))
    )
    (net (code "42") (name "/GREEN_H") (class "Default")
      (node (ref "H_R22") (pin "2") (pinfunction "2_2") (pintype "passive"))
      (node (ref "P_R24") (pin "1") (pinfunction "1_1") (pintype "passive"))
      (node (ref "U4") (pin "11") (pinfunction "G2A_11") (pintype "passive"))
      (node (ref "U4") (pin "5") (pinfunction "G1A_5") (pintype "passive"))
    )
    (net (code "43") (name "/G_PD_DET_N") (class "Default")
      (node (ref "P14") (pin "1") (pinfunction "1_1") (pintype "passive"))
      (node (ref "U3") (pin "6") (pinfunction "PA_6") (pintype "passive"))
    )
    (net (code "44") (name "/G_PD_DET_P") (class "Default")
      (node (ref "P14") (pin "2") (pinfunction "2_2") (pintype "passive"))
      (node (ref "U3") (pin "7") (pinfunction "PC_7") (pintype "passive"))
    )
    (net (code "45") (name "/G_TX_LED_0_N") (class "Default")
      (node (ref "H_R15") (pin "2") (pinfunction "2_2") (pintype "passive"))
      (node (ref "P13") (pin "5") (pinfunction "5_5") (pintype "passive"))
      (node (ref "U3") (pin "2") (pinfunction "RC_2") (pintype "passive"))
    )
    (net (code "46") (name "/G_TX_LED_0_P") (class "Default")
      (node (ref "H_R14") (pin "1") (pinfunction "1_1") (pintype "passive"))
      (node (ref "P13") (pin "4") (pinfunction "4_4") (pintype "passive"))
      (node (ref "U3") (pin "11") (pinfunction "IC_11") (pintype "passive"))
    )
    (net (code "47") (name "/G_TX_LED_1_N") (class "Default")
      (node (ref "H_R13") (pin "1") (pinfunction "1_1") (pintype "passive"))
      (node (ref "P13") (pin "2") (pinfunction "2_2") (pintype "passive"))
    )
    (net (code "48") (name "/G_TX_LED_1_P") (class "Default")
      (node (ref "P13") (pin "1") (pinfunction "1_1") (pintype "passive"))
      (node (ref "U3") (pin "10") (pinfunction "G3C_10") (pintype "passive"))
      (node (ref "U3") (pin "3") (pinfunction "G1C_3") (pintype "passive"))
      (node (ref "U3") (pin "8") (pinfunction "G2C_8") (pintype "passive"))
    )
    (net (code "49") (name "/H_PD_DET_N") (class "Default")
      (node (ref "P18") (pin "1") (pinfunction "1_1") (pintype "passive"))
      (node (ref "U4") (pin "10") (pinfunction "IPA_10") (pintype "passive"))
      (node (ref "U4") (pin "2") (pinfunction "BPA_2") (pintype "passive"))
    )
    (net (code "50") (name "/H_PD_DET_P") (class "Default")
      (node (ref "P18") (pin "2") (pinfunction "2_2") (pintype "passive"))
      (node (ref "U4") (pin "1") (pinfunction "BPC_1") (pintype "passive"))
      (node (ref "U4") (pin "3") (pinfunction "IPC_3") (pintype "passive"))
    )
    (net (code "51") (name "/H_TX_LED_0_N") (class "Default")
      (node (ref "H_R24") (pin "2") (pinfunction "2_2") (pintype "passive"))
      (node (ref "P17") (pin "5") (pinfunction "5_5") (pintype "passive"))
      (node (ref "U4") (pin "8") (pinfunction "RC_8") (pintype "passive"))
    )
    (net (code "52") (name "/H_TX_LED_0_P") (class "Default")
      (node (ref "H_R23") (pin "1") (pinfunction "1_1") (pintype "passive"))
      (node (ref "P17") (pin "4") (pinfunction "4_4") (pintype "passive"))
      (node (ref "U4") (pin "9") (pinfunction "IC_9") (pintype "passive"))
    )
    (net (code "53") (name "/H_TX_LED_1_N") (class "Default")
      (node (ref "H_R22") (pin "1") (pinfunction "1_1") (pintype "passive"))
      (node (ref "P17") (pin "2") (pinfunction "2_2") (pintype "passive"))
    )
    (net (code "54") (name "/H_TX_LED_1_P") (class "Default")
      (node (ref "P17") (pin "1") (pinfunction "1_1") (pintype "passive"))
      (node (ref "U4") (pin "12") (pinfunction "G2C_12") (pintype "passive"))
      (node (ref "U4") (pin "6") (pinfunction "G1C_6") (pintype "passive"))
    )
    (net (code "55") (name "/IR_E") (class "Default")
      (node (ref "H_R3") (pin "1") (pinfunction "1_1") (pintype "passive"))
      (node (ref "P_R1") (pin "1") (pinfunction "1_1") (pintype "passive"))
      (node (ref "U1") (pin "7") (pinfunction "IA_7") (pintype "passive"))
    )
    (net (code "56") (name "/IR_G") (class "Default")
      (node (ref "H_R15") (pin "1") (pinfunction "1_1") (pintype "passive"))
      (node (ref "P_R12") (pin "1") (pinfunction "1_1") (pintype "passive"))
      (node (ref "U3") (pin "12") (pinfunction "IA_12") (pintype "passive"))
    )
    (net (code "57") (name "/IR_H") (class "Default")
      (node (ref "H_R24") (pin "1") (pinfunction "1_1") (pintype "passive"))
      (node (ref "P_R22") (pin "1") (pinfunction "1_1") (pintype "passive"))
      (node (ref "U4") (pin "4") (pinfunction "IA_4") (pintype "passive"))
    )
    (net (code "58") (name "/RED_E") (class "Default")
      (node (ref "H_R1") (pin "2") (pinfunction "2_2") (pintype "passive"))
      (node (ref "P_R2") (pin "1") (pinfunction "1_1") (pintype "passive"))
      (node (ref "U1") (pin "3") (pinfunction "RA_3") (pintype "passive"))
    )
    (net (code "59") (name "/RED_G") (class "Default")
      (node (ref "H_R14") (pin "2") (pinfunction "2_2") (pintype "passive"))
      (node (ref "P_R16") (pin "1") (pinfunction "1_1") (pintype "passive"))
      (node (ref "U3") (pin "1") (pinfunction "RA_1") (pintype "passive"))
    )
    (net (code "60") (name "/RED_H") (class "Default")
      (node (ref "H_R23") (pin "2") (pinfunction "2_2") (pintype "passive"))
      (node (ref "P_R25") (pin "1") (pinfunction "1_1") (pintype "passive"))
      (node (ref "U4") (pin "7") (pinfunction "RA_7") (pintype "passive"))
    )
    (net (code "61") (name "/TX_LED_0_N") (class "Default")
      (node (ref "J1") (pin "3") (pinfunction "3_3") (pintype "passive"))
      (node (ref "SW1") (pin "5") (pinfunction "COMMON2_5") (pintype "passive"))
    )
    (net (code "62") (name "/TX_LED_0_P") (class "Default")
      (node (ref "J1") (pin "2") (pinfunction "2_2") (pintype "passive"))
      (node (ref "SW1") (pin "2") (pinfunction "COMMON1_2") (pintype "passive"))
    )
    (net (code "63") (name "/TX_LED_1_N") (class "Default")
      (node (ref "J1") (pin "6") (pinfunction "6_6") (pintype "passive"))
      (node (ref "P3") (pin "2") (pinfunction "2_2") (pintype "passive"))
      (node (ref "SW1") (pin "6") (pinfunction "NO2_6") (pintype "passive"))
    )
    (net (code "64") (name "/TX_LED_1_P") (class "Default")
      (node (ref "J1") (pin "1") (pinfunction "1_1") (pintype "passive"))
      (node (ref "P3") (pin "1") (pinfunction "1_1") (pintype "passive"))
      (node (ref "SW1") (pin "3") (pinfunction "NO1_3") (pintype "passive"))
    )
    (net (code "65") (name "/TX_LED_A_0_N") (class "Default")
      (node (ref "P3") (pin "5") (pinfunction "5_5") (pintype "passive"))
      (node (ref "SW1") (pin "4") (pinfunction "NC2_4") (pintype "passive"))
    )
    (net (code "66") (name "/TX_LED_A_0_P") (class "Default")
      (node (ref "P3") (pin "4") (pinfunction "4_4") (pintype "passive"))
      (node (ref "SW1") (pin "1") (pinfunction "NC1_1") (pintype "passive"))
    )
    (net (code "67") (name "GND") (class "Default")
      (node (ref "J1") (pin "10") (pinfunction "MH1_10") (pintype "passive"))
      (node (ref "J1") (pin "11") (pinfunction "MH2_11") (pintype "passive"))
      (node (ref "J1") (pin "7") (pinfunction "7_7") (pintype "passive"))
      (node (ref "P6") (pin "4") (pinfunction "4_4") (pintype "passive"))
      (node (ref "P6") (pin "5") (pinfunction "5_5") (pintype "passive"))
    )
    (net (code "68") (name "GND_A") (class "Default")
      (node (ref "P10") (pin "4") (pinfunction "4_4") (pintype "passive"))
      (node (ref "P10") (pin "5") (pinfunction "5_5") (pintype "passive"))
    )
    (net (code "69") (name "GND_B") (class "Default")
      (node (ref "P16") (pin "4") (pinfunction "4_4") (pintype "passive"))
      (node (ref "P16") (pin "5") (pinfunction "5_5") (pintype "passive"))
    )
    (net (code "70") (name "GND_C") (class "Default")
      (node (ref "P5") (pin "4") (pinfunction "4_4") (pintype "passive"))
      (node (ref "P5") (pin "5") (pinfunction "5_5") (pintype "passive"))
    )
    (net (code "71") (name "GND_D") (class "Default")
      (node (ref "P12") (pin "4") (pinfunction "4_4") (pintype "passive"))
      (node (ref "P12") (pin "5") (pinfunction "5_5") (pintype "passive"))
    )
    (net (code "72") (name "GND_E") (class "Default")
      (node (ref "P4") (pin "4") (pinfunction "4_4") (pintype "passive"))
      (node (ref "P4") (pin "5") (pinfunction "5_5") (pintype "passive"))
    )
    (net (code "73") (name "GND_F") (class "Default")
      (node (ref "P8") (pin "4") (pinfunction "4_4") (pintype "passive"))
      (node (ref "P8") (pin "5") (pinfunction "5_5") (pintype "passive"))
    )
    (net (code "74") (name "GND_G") (class "Default")
      (node (ref "P14") (pin "4") (pinfunction "4_4") (pintype "passive"))
      (node (ref "P14") (pin "5") (pinfunction "5_5") (pintype "passive"))
    )
    (net (code "75") (name "GND_H") (class "Default")
      (node (ref "P18") (pin "4") (pinfunction "4_4") (pintype "passive"))
      (node (ref "P18") (pin "5") (pinfunction "5_5") (pintype "passive"))
    )
    (net (code "76") (name "Net-(G_LED1-Pad1)") (class "Default")
      (node (ref "G_LED1") (pin "1") (pinfunction "1_1") (pintype "passive"))
      (node (ref "H_R6") (pin "2") (pinfunction "2_2") (pintype "passive"))
      (node (ref "P_R7") (pin "1") (pinfunction "1_1") (pintype "passive"))
    )
    (net (code "77") (name "Net-(G_LED2-Pad1)") (class "Default")
      (node (ref "G_LED2") (pin "1") (pinfunction "1_1") (pintype "passive"))
      (node (ref "H_R11") (pin "2") (pinfunction "2_2") (pintype "passive"))
      (node (ref "P_R13") (pin "1") (pinfunction "1_1") (pintype "passive"))
    )
    (net (code "78") (name "Net-(G_LED3-Pad1)") (class "Default")
      (node (ref "G_LED3") (pin "1") (pinfunction "1_1") (pintype "passive"))
      (node (ref "H_R18") (pin "2") (pinfunction "2_2") (pintype "passive"))
      (node (ref "P_R19") (pin "1") (pinfunction "1_1") (pintype "passive"))
    )
    (net (code "79") (name "Net-(G_LED4-Pad1)") (class "Default")
      (node (ref "G_LED4") (pin "1") (pinfunction "1_1") (pintype "passive"))
      (node (ref "G_LED5") (pin "1") (pinfunction "1_1") (pintype "passive"))
      (node (ref "H_R26") (pin "2") (pinfunction "2_2") (pintype "passive"))
      (node (ref "P_R26") (pin "1") (pinfunction "1_1") (pintype "passive"))
    )
    (net (code "80") (name "Net-(H_R4-Pad2)") (class "Default")
      (node (ref "H_R4") (pin "2") (pinfunction "2_2") (pintype "passive"))
      (node (ref "P_R5") (pin "1") (pinfunction "1_1") (pintype "passive"))
      (node (ref "R_LED1") (pin "1") (pinfunction "1_1") (pintype "passive"))
    )
    (net (code "81") (name "Net-(H_R5-Pad1)") (class "Default")
      (node (ref "H_R5") (pin "1") (pinfunction "1_1") (pintype "passive"))
      (node (ref "IR_LED1") (pin "1") (pinfunction "1_1") (pintype "passive"))
      (node (ref "P_R4") (pin "1") (pinfunction "1_1") (pintype "passive"))
    )
    (net (code "82") (name "Net-(H_R7-Pad1)") (class "Default")
      (node (ref "H_R7") (pin "1") (pinfunction "1_1") (pintype "passive"))
      (node (ref "P_R6") (pin "1") (pinfunction "1_1") (pintype "passive"))
      (node (ref "Y_LED1") (pin "1") (pinfunction "1_1") (pintype "passive"))
    )
    (net (code "83") (name "Net-(H_R9-Pad2)") (class "Default")
      (node (ref "H_R9") (pin "2") (pinfunction "2_2") (pintype "passive"))
      (node (ref "P_R10") (pin "1") (pinfunction "1_1") (pintype "passive"))
      (node (ref "R_LED2") (pin "1") (pinfunction "1_1") (pintype "passive"))
    )
    (net (code "84") (name "Net-(H_R10-Pad1)") (class "Default")
      (node (ref "H_R10") (pin "1") (pinfunction "1_1") (pintype "passive"))
      (node (ref "IR_LED2") (pin "1") (pinfunction "1_1") (pintype "passive"))
      (node (ref "P_R9") (pin "1") (pinfunction "1_1") (pintype "passive"))
    )
    (net (code "85") (name "Net-(H_R12-Pad1)") (class "Default")
      (node (ref "H_R12") (pin "1") (pinfunction "1_1") (pintype "passive"))
      (node (ref "P_R11") (pin "1") (pinfunction "1_1") (pintype "passive"))
      (node (ref "Y_LED2") (pin "1") (pinfunction "1_1") (pintype "passive"))
    )
    (net (code "86") (name "Net-(H_R16-Pad2)") (class "Default")
      (node (ref "H_R16") (pin "2") (pinfunction "2_2") (pintype "passive"))
      (node (ref "P_R17") (pin "1") (pinfunction "1_1") (pintype "passive"))
      (node (ref "R_LED3") (pin "1") (pinfunction "1_1") (pintype "passive"))
    )
    (net (code "87") (name "Net-(H_R17-Pad1)") (class "Default")
      (node (ref "H_R17") (pin "1") (pinfunction "1_1") (pintype "passive"))
      (node (ref "IR_LED3") (pin "1") (pinfunction "1_1") (pintype "passive"))
      (node (ref "P_R15") (pin "1") (pinfunction "1_1") (pintype "passive"))
    )
    (net (code "88") (name "Net-(H_R19-Pad1)") (class "Default")
      (node (ref "H_R19") (pin "1") (pinfunction "1_1") (pintype "passive"))
      (node (ref "P_R18") (pin "1") (pinfunction "1_1") (pintype "passive"))
      (node (ref "Y_LED3") (pin "1") (pinfunction "1_1") (pintype "passive"))
    )
    (net (code "89") (name "Net-(H_R20-Pad1)") (class "Default")
      (node (ref "H_R20") (pin "1") (pinfunction "1_1") (pintype "passive"))
      (node (ref "IR_LED4") (pin "1") (pinfunction "1_1") (pintype "passive"))
      (node (ref "IR_LED5") (pin "1") (pinfunction "1_1") (pintype "passive"))
      (node (ref "P_R20") (pin "2") (pinfunction "2_2") (pintype "passive"))
    )
    (net (code "90") (name "Net-(H_R21-Pad2)") (class "Default")
      (node (ref "H_R21") (pin "2") (pinfunction "2_2") (pintype "passive"))
      (node (ref "P_R21") (pin "1") (pinfunction "1_1") (pintype "passive"))
      (node (ref "R_LED4") (pin "1") (pinfunction "1_1") (pintype "passive"))
      (node (ref "R_LED5") (pin "1") (pinfunction "1_1") (pintype "passive"))
    )
    (net (code "91") (name "Net-(H_R25-Pad1)") (class "Default")
      (node (ref "H_R25") (pin "1") (pinfunction "1_1") (pintype "passive"))
      (node (ref "P_R23") (pin "2") (pinfunction "2_2") (pintype "passive"))
      (node (ref "Y_LED4") (pin "1") (pinfunction "1_1") (pintype "passive"))
      (node (ref "Y_LED5") (pin "1") (pinfunction "1_1") (pintype "passive"))
    )
    (net (code "92") (name "Net-(U2-G2A)") (class "Default")
      (node (ref "C_R1") (pin "2") (pinfunction "2_2") (pintype "passive"))
      (node (ref "U2") (pin "4") (pinfunction "G2A_4") (pintype "passive"))
    )
    (net (code "93") (name "VDD_LED") (class "Default")
      (node (ref "J1") (pin "4") (pinfunction "4_4") (pintype "passive"))
      (node (ref "J1") (pin "8") (pinfunction "8_8") (pintype "passive"))
      (node (ref "P3") (pin "3") (pinfunction "3_3") (pintype "passive"))
      (node (ref "P6") (pin "3") (pinfunction "3_3") (pintype "passive"))
    )
    (net (code "94") (name "VDD_LED_A") (class "Default")
      (node (ref "P9") (pin "3") (pinfunction "3_3") (pintype "passive"))
      (node (ref "P_R11") (pin "2") (pinfunction "2_2") (pintype "passive"))
      (node (ref "P_R13") (pin "2") (pinfunction "2_2") (pintype "passive"))
    )
    (net (code "95") (name "VDD_LED_A_0") (class "Default")
      (node (ref "P10") (pin "3") (pinfunction "3_3") (pintype "passive"))
      (node (ref "P_R10") (pin "2") (pinfunction "2_2") (pintype "passive"))
      (node (ref "P_R9") (pin "2") (pinfunction "2_2") (pintype "passive"))
    )
    (net (code "96") (name "VDD_LED_B") (class "Default")
      (node (ref "P15") (pin "3") (pinfunction "3_3") (pintype "passive"))
      (node (ref "P_R23") (pin "1") (pinfunction "1_1") (pintype "passive"))
      (node (ref "P_R26") (pin "2") (pinfunction "2_2") (pintype "passive"))
    )
    (net (code "97") (name "VDD_LED_B_0") (class "Default")
      (node (ref "P16") (pin "3") (pinfunction "3_3") (pintype "passive"))
      (node (ref "P_R20") (pin "1") (pinfunction "1_1") (pintype "passive"))
      (node (ref "P_R21") (pin "2") (pinfunction "2_2") (pintype "passive"))
    )
    (net (code "98") (name "VDD_LED_C") (class "Default")
      (node (ref "P2") (pin "3") (pinfunction "3_3") (pintype "passive"))
      (node (ref "P_R6") (pin "2") (pinfunction "2_2") (pintype "passive"))
      (node (ref "P_R7") (pin "2") (pinfunction "2_2") (pintype "passive"))
    )
    (net (code "99") (name "VDD_LED_C_0") (class "Default")
      (node (ref "P5") (pin "3") (pinfunction "3_3") (pintype "passive"))
      (node (ref "P_R4") (pin "2") (pinfunction "2_2") (pintype "passive"))
      (node (ref "P_R5") (pin "2") (pinfunction "2_2") (pintype "passive"))
    )
    (net (code "100") (name "VDD_LED_D") (class "Default")
      (node (ref "P11") (pin "3") (pinfunction "3_3") (pintype "passive"))
      (node (ref "P_R18") (pin "2") (pinfunction "2_2") (pintype "passive"))
      (node (ref "P_R19") (pin "2") (pinfunction "2_2") (pintype "passive"))
    )
    (net (code "101") (name "VDD_LED_D_0") (class "Default")
      (node (ref "P12") (pin "3") (pinfunction "3_3") (pintype "passive"))
      (node (ref "P_R15") (pin "2") (pinfunction "2_2") (pintype "passive"))
      (node (ref "P_R17") (pin "2") (pinfunction "2_2") (pintype "passive"))
    )
    (net (code "102") (name "VDD_LED_E") (class "Default")
      (node (ref "P1") (pin "3") (pinfunction "3_3") (pintype "passive"))
      (node (ref "P_R3") (pin "2") (pinfunction "2_2") (pintype "passive"))
    )
    (net (code "103") (name "VDD_LED_E_0") (class "Default")
      (node (ref "P4") (pin "3") (pinfunction "3_3") (pintype "passive"))
      (node (ref "P_R1") (pin "2") (pinfunction "2_2") (pintype "passive"))
      (node (ref "P_R2") (pin "2") (pinfunction "2_2") (pintype "passive"))
    )
    (net (code "104") (name "VDD_LED_F") (class "Default")
      (node (ref "P7") (pin "3") (pinfunction "3_3") (pintype "passive"))
      (node (ref "P_R8") (pin "2") (pinfunction "2_2") (pintype "passive"))
    )
    (net (code "105") (name "VDD_LED_F_0") (class "Default")
      (node (ref "P8") (pin "3") (pinfunction "3_3") (pintype "passive"))
    )
    (net (code "106") (name "VDD_LED_G") (class "Default")
      (node (ref "P13") (pin "3") (pinfunction "3_3") (pintype "passive"))
      (node (ref "P_R14") (pin "2") (pinfunction "2_2") (pintype "passive"))
    )
    (net (code "107") (name "VDD_LED_G_0") (class "Default")
      (node (ref "P14") (pin "3") (pinfunction "3_3") (pintype "passive"))
      (node (ref "P_R12") (pin "2") (pinfunction "2_2") (pintype "passive"))
      (node (ref "P_R16") (pin "2") (pinfunction "2_2") (pintype "passive"))
    )
    (net (code "108") (name "VDD_LED_H") (class "Default")
      (node (ref "P17") (pin "3") (pinfunction "3_3") (pintype "passive"))
      (node (ref "P_R24") (pin "2") (pinfunction "2_2") (pintype "passive"))
    )
    (net (code "109") (name "VDD_LED_H_0") (class "Default")
      (node (ref "P18") (pin "3") (pinfunction "3_3") (pintype "passive"))
      (node (ref "P_R22") (pin "2") (pinfunction "2_2") (pintype "passive"))
      (node (ref "P_R25") (pin "2") (pinfunction "2_2") (pintype "passive"))
    )
  )
)
